# StepperDriver.net
KiCad netlist of a schematic drawn in Altium Designer
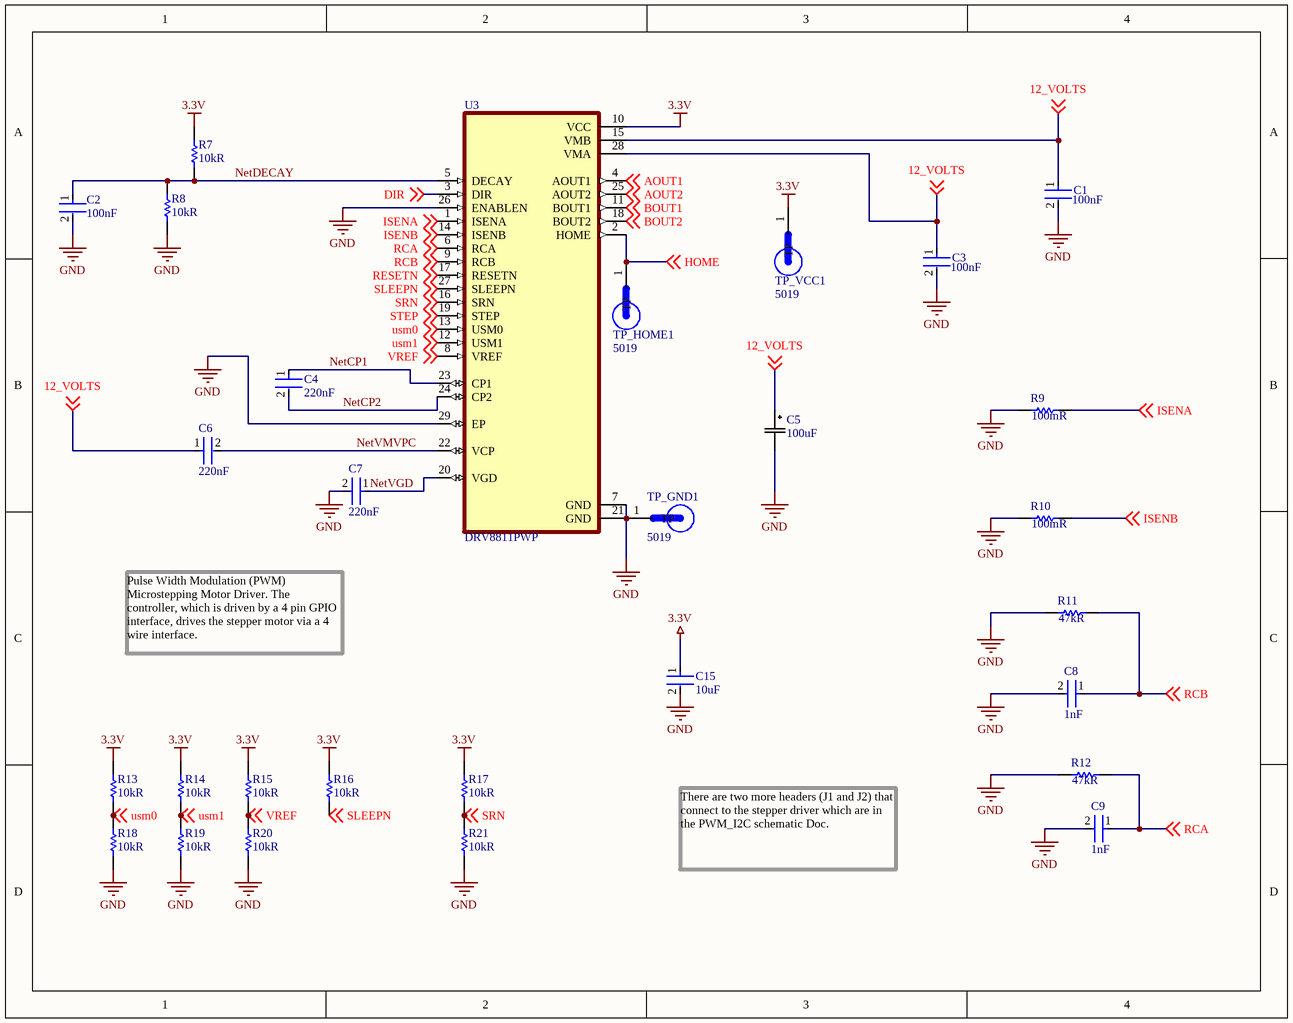
[diagram p0: StepperDriver.SchDoc]

(export (version "E")
  (design (tool "Eeschema 10.0.6"))
  (components
    (comp (ref "C1")
      (value "CL21B104KACNNNC")
      (footprint "FP-CL21-IPC_C")
      (description "CL21 Series 0805 100nF 25V ±10% Tolerance X7R Multilayer Ceramic Chip Capacitor")
      (fields
        (field (name "CAPACITANCE") "100nF")
        (field (name "VOLTAGE") "25V")
        (field (name "TOLERANCE") "10%")
      )
      (libsource (lib "Altium Content Vault") (part "b4654b650e69147ec39a6b967a45e02"))
    )
    (comp (ref "C2")
      (value "CL21B104KACNNNC")
      (footprint "FP-CL21-IPC_C")
      (description "CL21 Series 0805 100nF 25V ±10% Tolerance X7R Multilayer Ceramic Chip Capacitor")
      (fields
        (field (name "CAPACITANCE") "100nF")
        (field (name "VOLTAGE") "25V")
        (field (name "TOLERANCE") "10%")
      )
      (libsource (lib "Altium Content Vault") (part "b4654b650e69147ec39a6b967a45e02"))
    )
    (comp (ref "C3")
      (value "CL21B104KACNNNC")
      (footprint "FP-CL21-IPC_C")
      (description "CL21 Series 0805 100nF 25V ±10% Tolerance X7R Multilayer Ceramic Chip Capacitor")
      (fields
        (field (name "CAPACITANCE") "100nF")
        (field (name "VOLTAGE") "25V")
        (field (name "TOLERANCE") "10%")
      )
      (libsource (lib "Altium Content Vault") (part "b4654b650e69147ec39a6b967a45e02"))
    )
    (comp (ref "C4")
      (value "UMK212B7224KG-T")
      (footprint "FP-0805-L_2_0_0_1-W_1_25-IPC_A")
      (description "Multilayer Ceramic Capacitor 0.22 uF 50V X7R 10% SMD 0805 T/R")
      (fields
        (field (name "TOLERANCE") "10%")
        (field (name "VOLTAGE") "50V")
        (field (name "CAPACITANCE") "220nF")
      )
      (libsource (lib "Altium Content Vault") (part "b4654b650e69147ec39a6b967a45e02"))
    )
    (comp (ref "C5")
      (value "PCV1D101MCL2GS")
      (footprint "CAP_PC_8X7_NCH")
      (description "Cap Aluminum Polymer 100uF 20VDC 20% (8 X 7mm) SMD 0.042 Ohm 1400mA 3000h 105C Automotive T/R")
      (fields
        (field (name "MANUFACTURER") "Nichicon")
        (field (name "CAPACITANCE") "100uF")
        (field (name "TOLERANCE") "20%")
        (field (name "COPYRIGHT") "Copyright (C) 2022 Ultra Librarian. All rights reserved.")
      )
      (libsource (lib "PCV1D101MCL2GS") (part "PCV1D101MCL2GS"))
    )
    (comp (ref "C6")
      (value "UMK212B7224KG-T")
      (footprint "FP-0805-L_2_0_0_1-W_1_25-IPC_A")
      (description "Multilayer Ceramic Capacitor 0.22 uF 50V X7R 10% SMD 0805 T/R")
      (fields
        (field (name "TOLERANCE") "10%")
        (field (name "VOLTAGE") "50V")
        (field (name "CAPACITANCE") "220nF")
      )
      (libsource (lib "Altium Content Vault") (part "b4654b650e69147ec39a6b967a45e02"))
    )
    (comp (ref "C7")
      (value "UMK212B7224KG-T")
      (footprint "FP-0805-L_2_0_0_1-W_1_25-IPC_A")
      (description "Multilayer Ceramic Capacitor 0.22 uF 50V X7R 10% SMD 0805 T/R")
      (fields
        (field (name "TOLERANCE") "10%")
        (field (name "VOLTAGE") "50V")
        (field (name "CAPACITANCE") "220nF")
      )
      (libsource (lib "Altium Content Vault") (part "b4654b650e69147ec39a6b967a45e02"))
    )
    (comp (ref "C8")
      (value "08055C102KAT2A")
      (footprint "FP-0805-L_2_01_0_2-W_1_25-IPC_C")
      (description "General Purpose Ceramic Capacitor, 0805, 1nF, 10%, X7R, 0.15, 50V")
      (fields
        (field (name "VOLTAGE") "50V")
        (field (name "TOLERANCE") "10%")
        (field (name "CAPACITANCE") "1nF")
      )
      (libsource (lib "Altium Content Vault") (part "02cd4be3c70576c341d710602a673aa"))
    )
    (comp (ref "C9")
      (value "08055C102KAT2A")
      (footprint "FP-0805-L_2_01_0_2-W_1_25-IPC_C")
      (description "General Purpose Ceramic Capacitor, 0805, 1nF, 10%, X7R, 0.15, 50V")
      (fields
        (field (name "VOLTAGE") "50V")
        (field (name "TOLERANCE") "10%")
        (field (name "CAPACITANCE") "1nF")
      )
      (libsource (lib "Altium Content Vault") (part "02cd4be3c70576c341d710602a673aa"))
    )
    (comp (ref "C15")
      (value "10uF")
      (footprint "FP-C0805C-DG-MFG")
      (description "CAP CER 10UF 10V X5R 0805")
      (fields (field (name "TOLERANCE") "10%") (field (name "MANUFACTURER PART NUMBER") "C0805C106K8PACTU"))
      (libsource (lib "Altium Content Vault") (part "11868f565c42a9108669ba33697ecf6"))
    )
    (comp (ref "R7")
      (value "RC0805FR-0710KL")
      (footprint "RESC2013X60X35NL10T20")
      (description "Chip Resistor, 10 KOhm, +/- 1%, 0.125 W, -55 to 155 degC, 0805 (2012 Metric), RoHS, Tape and Reel")
      (fields
        (field (name "MANUFACTURER") "Yageo")
        (field (name "RESISTANCE") "10kR")
        (field (name "TOLERANCE") "1%")
      )
      (libsource (lib "Altium Content Vault") (part "RES-2"))
    )
    (comp (ref "R8")
      (value "RC0805FR-0710KL")
      (footprint "RESC2013X60X35NL10T20")
      (description "Chip Resistor, 10 KOhm, +/- 1%, 0.125 W, -55 to 155 degC, 0805 (2012 Metric), RoHS, Tape and Reel")
      (fields
        (field (name "MANUFACTURER") "Yageo")
        (field (name "RESISTANCE") "10kR")
        (field (name "TOLERANCE") "1%")
      )
      (libsource (lib "Altium Content Vault") (part "RES-2"))
    )
    (comp (ref "R9")
      (value "PT0805FR-7W0R1L")
      (footprint "RESC2013X65X35ML10T20")
      (fields
        (field (name "MANUFACTURER") "Yageo")
        (field (name "RESISTANCE") "100mR")
        (field (name "TOLERANCE") "1%")
      )
      (libsource (lib "Altium Content Vault") (part "RES"))
    )
    (comp (ref "R10")
      (value "PT0805FR-7W0R1L")
      (footprint "RESC2013X65X35ML10T20")
      (fields
        (field (name "MANUFACTURER") "Yageo")
        (field (name "RESISTANCE") "100mR")
        (field (name "TOLERANCE") "1%")
      )
      (libsource (lib "Altium Content Vault") (part "RES"))
    )
    (comp (ref "R11")
      (value "ERJ-6GEYJ473V")
      (footprint "RESC2013X70X40ML20T20")
      (fields
        (field (name "MANUFACTURER") "Panasonic")
        (field (name "TOLERANCE") "5%")
        (field (name "RESISTANCE") "47kR")
      )
      (libsource (lib "Altium Content Vault") (part "RES"))
    )
    (comp (ref "R12")
      (value "ERJ-6GEYJ473V")
      (footprint "RESC2013X70X40ML20T20")
      (fields
        (field (name "MANUFACTURER") "Panasonic")
        (field (name "TOLERANCE") "5%")
        (field (name "RESISTANCE") "47kR")
      )
      (libsource (lib "Altium Content Vault") (part "RES"))
    )
    (comp (ref "R13")
      (value "RC0805FR-0710KL")
      (footprint "RESC2013X60X35NL10T20")
      (description "Chip Resistor, 10 KOhm, +/- 1%, 0.125 W, -55 to 155 degC, 0805 (2012 Metric), RoHS, Tape and Reel")
      (fields
        (field (name "MANUFACTURER") "Yageo")
        (field (name "RESISTANCE") "10kR")
        (field (name "TOLERANCE") "1%")
      )
      (libsource (lib "Altium Content Vault") (part "RES-2"))
    )
    (comp (ref "R14")
      (value "RC0805FR-0710KL")
      (footprint "RESC2013X60X35NL10T20")
      (description "Chip Resistor, 10 KOhm, +/- 1%, 0.125 W, -55 to 155 degC, 0805 (2012 Metric), RoHS, Tape and Reel")
      (fields
        (field (name "MANUFACTURER") "Yageo")
        (field (name "RESISTANCE") "10kR")
        (field (name "TOLERANCE") "1%")
      )
      (libsource (lib "Altium Content Vault") (part "RES-2"))
    )
    (comp (ref "R15")
      (value "RC0805FR-0710KL")
      (footprint "RESC2013X60X35NL10T20")
      (description "Chip Resistor, 10 KOhm, +/- 1%, 0.125 W, -55 to 155 degC, 0805 (2012 Metric), RoHS, Tape and Reel")
      (fields
        (field (name "MANUFACTURER") "Yageo")
        (field (name "RESISTANCE") "10kR")
        (field (name "TOLERANCE") "1%")
      )
      (libsource (lib "Altium Content Vault") (part "RES-2"))
    )
    (comp (ref "R16")
      (value "RC0805FR-0710KL")
      (footprint "RESC2013X60X35NL10T20")
      (description "Chip Resistor, 10 KOhm, +/- 1%, 0.125 W, -55 to 155 degC, 0805 (2012 Metric), RoHS, Tape and Reel")
      (fields
        (field (name "MANUFACTURER") "Yageo")
        (field (name "RESISTANCE") "10kR")
        (field (name "TOLERANCE") "1%")
      )
      (libsource (lib "Altium Content Vault") (part "RES-2"))
    )
    (comp (ref "R17")
      (value "RC0805FR-0710KL")
      (footprint "RESC2013X60X35NL10T20")
      (description "Chip Resistor, 10 KOhm, +/- 1%, 0.125 W, -55 to 155 degC, 0805 (2012 Metric), RoHS, Tape and Reel")
      (fields
        (field (name "MANUFACTURER") "Yageo")
        (field (name "RESISTANCE") "10kR")
        (field (name "TOLERANCE") "1%")
      )
      (libsource (lib "Altium Content Vault") (part "RES-2"))
    )
    (comp (ref "R18")
      (value "RC0805FR-0710KL")
      (footprint "RESC2013X60X35NL10T20")
      (description "Chip Resistor, 10 KOhm, +/- 1%, 0.125 W, -55 to 155 degC, 0805 (2012 Metric), RoHS, Tape and Reel")
      (fields
        (field (name "MANUFACTURER") "Yageo")
        (field (name "RESISTANCE") "10kR")
        (field (name "TOLERANCE") "1%")
      )
      (libsource (lib "Altium Content Vault") (part "RES-2"))
    )
    (comp (ref "R19")
      (value "RC0805FR-0710KL")
      (footprint "RESC2013X60X35NL10T20")
      (description "Chip Resistor, 10 KOhm, +/- 1%, 0.125 W, -55 to 155 degC, 0805 (2012 Metric), RoHS, Tape and Reel")
      (fields
        (field (name "MANUFACTURER") "Yageo")
        (field (name "RESISTANCE") "10kR")
        (field (name "TOLERANCE") "1%")
      )
      (libsource (lib "Altium Content Vault") (part "RES-2"))
    )
    (comp (ref "R20")
      (value "RC0805FR-0710KL")
      (footprint "RESC2013X60X35NL10T20")
      (description "Chip Resistor, 10 KOhm, +/- 1%, 0.125 W, -55 to 155 degC, 0805 (2012 Metric), RoHS, Tape and Reel")
      (fields
        (field (name "MANUFACTURER") "Yageo")
        (field (name "RESISTANCE") "10kR")
        (field (name "TOLERANCE") "1%")
      )
      (libsource (lib "Altium Content Vault") (part "RES-2"))
    )
    (comp (ref "R21")
      (value "RC0805FR-0710KL")
      (footprint "RESC2013X60X35NL10T20")
      (description "Chip Resistor, 10 KOhm, +/- 1%, 0.125 W, -55 to 155 degC, 0805 (2012 Metric), RoHS, Tape and Reel")
      (fields
        (field (name "MANUFACTURER") "Yageo")
        (field (name "RESISTANCE") "10kR")
        (field (name "TOLERANCE") "1%")
      )
      (libsource (lib "Altium Content Vault") (part "RES-2"))
    )
    (comp (ref "TP_GND1")
      (value "5019")
      (footprint "TP380X203")
      (description "PC Test Point, Miniature Phosphor Bronze, Silver Plating Surface Mount Mounting Type")
      (fields (field (name "MF") "Keystone Electronics") (field (name "DIGI-KEY_PART_NUMBER") "36-5019CT-ND"))
      (libsource (lib "5019TP") (part "5019"))
    )
    (comp (ref "TP_HOME1")
      (value "5019")
      (footprint "TP380X203")
      (description "PC Test Point, Miniature Phosphor Bronze, Silver Plating Surface Mount Mounting Type")
      (fields (field (name "MF") "Keystone Electronics") (field (name "DIGI-KEY_PART_NUMBER") "36-5019CT-ND"))
      (libsource (lib "5019TP") (part "5019"))
    )
    (comp (ref "TP_VCC1")
      (value "5019")
      (footprint "TP380X203")
      (description "PC Test Point, Miniature Phosphor Bronze, Silver Plating Surface Mount Mounting Type")
      (fields (field (name "MF") "Keystone Electronics") (field (name "DIGI-KEY_PART_NUMBER") "36-5019CT-ND"))
      (libsource (lib "5019TP") (part "5019"))
    )
    (comp (ref "U3")
      (value "DRV8811PWP")
      (footprint "IC_TPS61196PWPRQ1")
      (fields (field (name "MF") "Texas Instruments"))
      (libsource (lib "DRV8811PWP") (part "DRV8811PWP"))
    )
  )
  (nets
    (net (code "1") (name "/NetCP1") (class "Default")
      (node (ref "C4") (pin "1") (pinfunction "1_1") (pintype "passive"))
      (node (ref "U3") (pin "23") (pinfunction "CP1_23") (pintype "bidirectional"))
    )
    (net (code "2") (name "/NetCP2") (class "Default")
      (node (ref "C4") (pin "2") (pinfunction "2_2") (pintype "passive"))
      (node (ref "U3") (pin "24") (pinfunction "CP2_24") (pintype "bidirectional"))
    )
    (net (code "3") (name "/NetDECAY") (class "Default")
      (node (ref "C2") (pin "1") (pinfunction "1_1") (pintype "passive"))
      (node (ref "R7") (pin "1") (pinfunction "1_1") (pintype "passive"))
      (node (ref "R8") (pin "2") (pinfunction "2_2") (pintype "passive"))
      (node (ref "U3") (pin "5") (pinfunction "DECAY_5") (pintype "input"))
    )
    (net (code "4") (name "/NetVGD") (class "Default")
      (node (ref "C7") (pin "1") (pinfunction "1_1") (pintype "passive"))
      (node (ref "U3") (pin "20") (pinfunction "VGD_20") (pintype "bidirectional"))
    )
    (net (code "5") (name "/NetVMVPC") (class "Default")
      (node (ref "C6") (pin "2") (pinfunction "2_2") (pintype "passive"))
      (node (ref "U3") (pin "22") (pinfunction "VCP_22") (pintype "bidirectional"))
    )
    (net (code "6") (name "3.3V") (class "Default")
      (node (ref "C15") (pin "1") (pinfunction "1_1") (pintype "passive"))
      (node (ref "R13") (pin "2") (pinfunction "2_2") (pintype "passive"))
      (node (ref "R14") (pin "2") (pinfunction "2_2") (pintype "passive"))
      (node (ref "R15") (pin "2") (pinfunction "2_2") (pintype "passive"))
      (node (ref "R16") (pin "2") (pinfunction "2_2") (pintype "passive"))
      (node (ref "R17") (pin "2") (pinfunction "2_2") (pintype "passive"))
      (node (ref "R7") (pin "2") (pinfunction "2_2") (pintype "passive"))
      (node (ref "TP_VCC1") (pin "1") (pinfunction "TP_1") (pintype "passive"))
      (node (ref "U3") (pin "10") (pinfunction "VCC_10") (pintype "power_in"))
    )
    (net (code "7") (name "12_VOLTS") (class "Default")
      (node (ref "C1") (pin "1") (pinfunction "1_1") (pintype "passive"))
      (node (ref "C3") (pin "1") (pinfunction "1_1") (pintype "passive"))
      (node (ref "C5") (pin "1") (pinfunction "1_1") (pintype "passive"))
      (node (ref "C6") (pin "1") (pinfunction "1_1") (pintype "passive"))
      (node (ref "U3") (pin "15") (pinfunction "VMB_15") (pintype "power_in"))
      (node (ref "U3") (pin "28") (pinfunction "VMA_28") (pintype "power_in"))
    )
    (net (code "8") (name "AOUT1") (class "Default")
      (node (ref "U3") (pin "4") (pinfunction "AOUT1_4") (pintype "output"))
    )
    (net (code "9") (name "AOUT2") (class "Default")
      (node (ref "U3") (pin "25") (pinfunction "AOUT2_25") (pintype "output"))
    )
    (net (code "10") (name "BOUT1") (class "Default")
      (node (ref "U3") (pin "11") (pinfunction "BOUT1_11") (pintype "output"))
    )
    (net (code "11") (name "BOUT2") (class "Default")
      (node (ref "U3") (pin "18") (pinfunction "BOUT2_18") (pintype "output"))
    )
    (net (code "12") (name "DIR") (class "Default")
      (node (ref "U3") (pin "3") (pinfunction "DIR_3") (pintype "input"))
    )
    (net (code "13") (name "GND") (class "Default")
      (node (ref "C1") (pin "2") (pinfunction "2_2") (pintype "passive"))
      (node (ref "C15") (pin "2") (pinfunction "2_2") (pintype "passive"))
      (node (ref "C2") (pin "2") (pinfunction "2_2") (pintype "passive"))
      (node (ref "C3") (pin "2") (pinfunction "2_2") (pintype "passive"))
      (node (ref "C5") (pin "2") (pinfunction "2_2") (pintype "passive"))
      (node (ref "C7") (pin "2") (pinfunction "2_2") (pintype "passive"))
      (node (ref "C8") (pin "2") (pinfunction "2_2") (pintype "passive"))
      (node (ref "C9") (pin "2") (pinfunction "2_2") (pintype "passive"))
      (node (ref "R10") (pin "1") (pinfunction "1_1") (pintype "passive"))
      (node (ref "R11") (pin "1") (pinfunction "1_1") (pintype "passive"))
      (node (ref "R12") (pin "1") (pinfunction "1_1") (pintype "passive"))
      (node (ref "R18") (pin "1") (pinfunction "1_1") (pintype "passive"))
      (node (ref "R19") (pin "1") (pinfunction "1_1") (pintype "passive"))
      (node (ref "R20") (pin "1") (pinfunction "1_1") (pintype "passive"))
      (node (ref "R21") (pin "1") (pinfunction "1_1") (pintype "passive"))
      (node (ref "R8") (pin "1") (pinfunction "1_1") (pintype "passive"))
      (node (ref "R9") (pin "1") (pinfunction "1_1") (pintype "passive"))
      (node (ref "TP_GND1") (pin "1") (pinfunction "TP_1") (pintype "passive"))
      (node (ref "U3") (pin "21") (pinfunction "GND_21") (pintype "power_in"))
      (node (ref "U3") (pin "26") (pinfunction "ENABLEN_26") (pintype "input"))
      (node (ref "U3") (pin "29") (pinfunction "EP_29") (pintype "bidirectional"))
      (node (ref "U3") (pin "7") (pinfunction "GND_7") (pintype "power_in"))
    )
    (net (code "14") (name "HOME") (class "Default")
      (node (ref "TP_HOME1") (pin "1") (pinfunction "TP_1") (pintype "passive"))
      (node (ref "U3") (pin "2") (pinfunction "HOME_2") (pintype "output"))
    )
    (net (code "15") (name "ISENA") (class "Default")
      (node (ref "R9") (pin "2") (pinfunction "2_2") (pintype "passive"))
      (node (ref "U3") (pin "1") (pinfunction "ISENA_1") (pintype "input"))
    )
    (net (code "16") (name "ISENB") (class "Default")
      (node (ref "R10") (pin "2") (pinfunction "2_2") (pintype "passive"))
      (node (ref "U3") (pin "14") (pinfunction "ISENB_14") (pintype "input"))
    )
    (net (code "17") (name "RCA") (class "Default")
      (node (ref "C9") (pin "1") (pinfunction "1_1") (pintype "passive"))
      (node (ref "R12") (pin "2") (pinfunction "2_2") (pintype "passive"))
      (node (ref "U3") (pin "6") (pinfunction "RCA_6") (pintype "input"))
    )
    (net (code "18") (name "RCB") (class "Default")
      (node (ref "C8") (pin "1") (pinfunction "1_1") (pintype "passive"))
      (node (ref "R11") (pin "2") (pinfunction "2_2") (pintype "passive"))
      (node (ref "U3") (pin "9") (pinfunction "RCB_9") (pintype "input"))
    )
    (net (code "19") (name "RESETN") (class "Default")
      (node (ref "U3") (pin "17") (pinfunction "RESETN_17") (pintype "input"))
    )
    (net (code "20") (name "SLEEPN") (class "Default")
      (node (ref "R16") (pin "1") (pinfunction "1_1") (pintype "passive"))
      (node (ref "U3") (pin "27") (pinfunction "SLEEPN_27") (pintype "input"))
    )
    (net (code "21") (name "SRN") (class "Default")
      (node (ref "R17") (pin "1") (pinfunction "1_1") (pintype "passive"))
      (node (ref "R21") (pin "2") (pinfunction "2_2") (pintype "passive"))
      (node (ref "U3") (pin "16") (pinfunction "SRN_16") (pintype "input"))
    )
    (net (code "22") (name "STEP") (class "Default")
      (node (ref "U3") (pin "19") (pinfunction "STEP_19") (pintype "input"))
    )
    (net (code "23") (name "VREF") (class "Default")
      (node (ref "R15") (pin "1") (pinfunction "1_1") (pintype "passive"))
      (node (ref "R20") (pin "2") (pinfunction "2_2") (pintype "passive"))
      (node (ref "U3") (pin "8") (pinfunction "VREF_8") (pintype "input"))
    )
    (net (code "24") (name "usm0") (class "Default")
      (node (ref "R13") (pin "1") (pinfunction "1_1") (pintype "passive"))
      (node (ref "R18") (pin "2") (pinfunction "2_2") (pintype "passive"))
      (node (ref "U3") (pin "13") (pinfunction "USM0_13") (pintype "input"))
    )
    (net (code "25") (name "usm1") (class "Default")
      (node (ref "R14") (pin "1") (pinfunction "1_1") (pintype "passive"))
      (node (ref "R19") (pin "2") (pinfunction "2_2") (pintype "passive"))
      (node (ref "U3") (pin "12") (pinfunction "USM1_12") (pintype "input"))
    )
  )
)
